# usb.net
KiCad netlist of a schematic drawn in Altium Designer
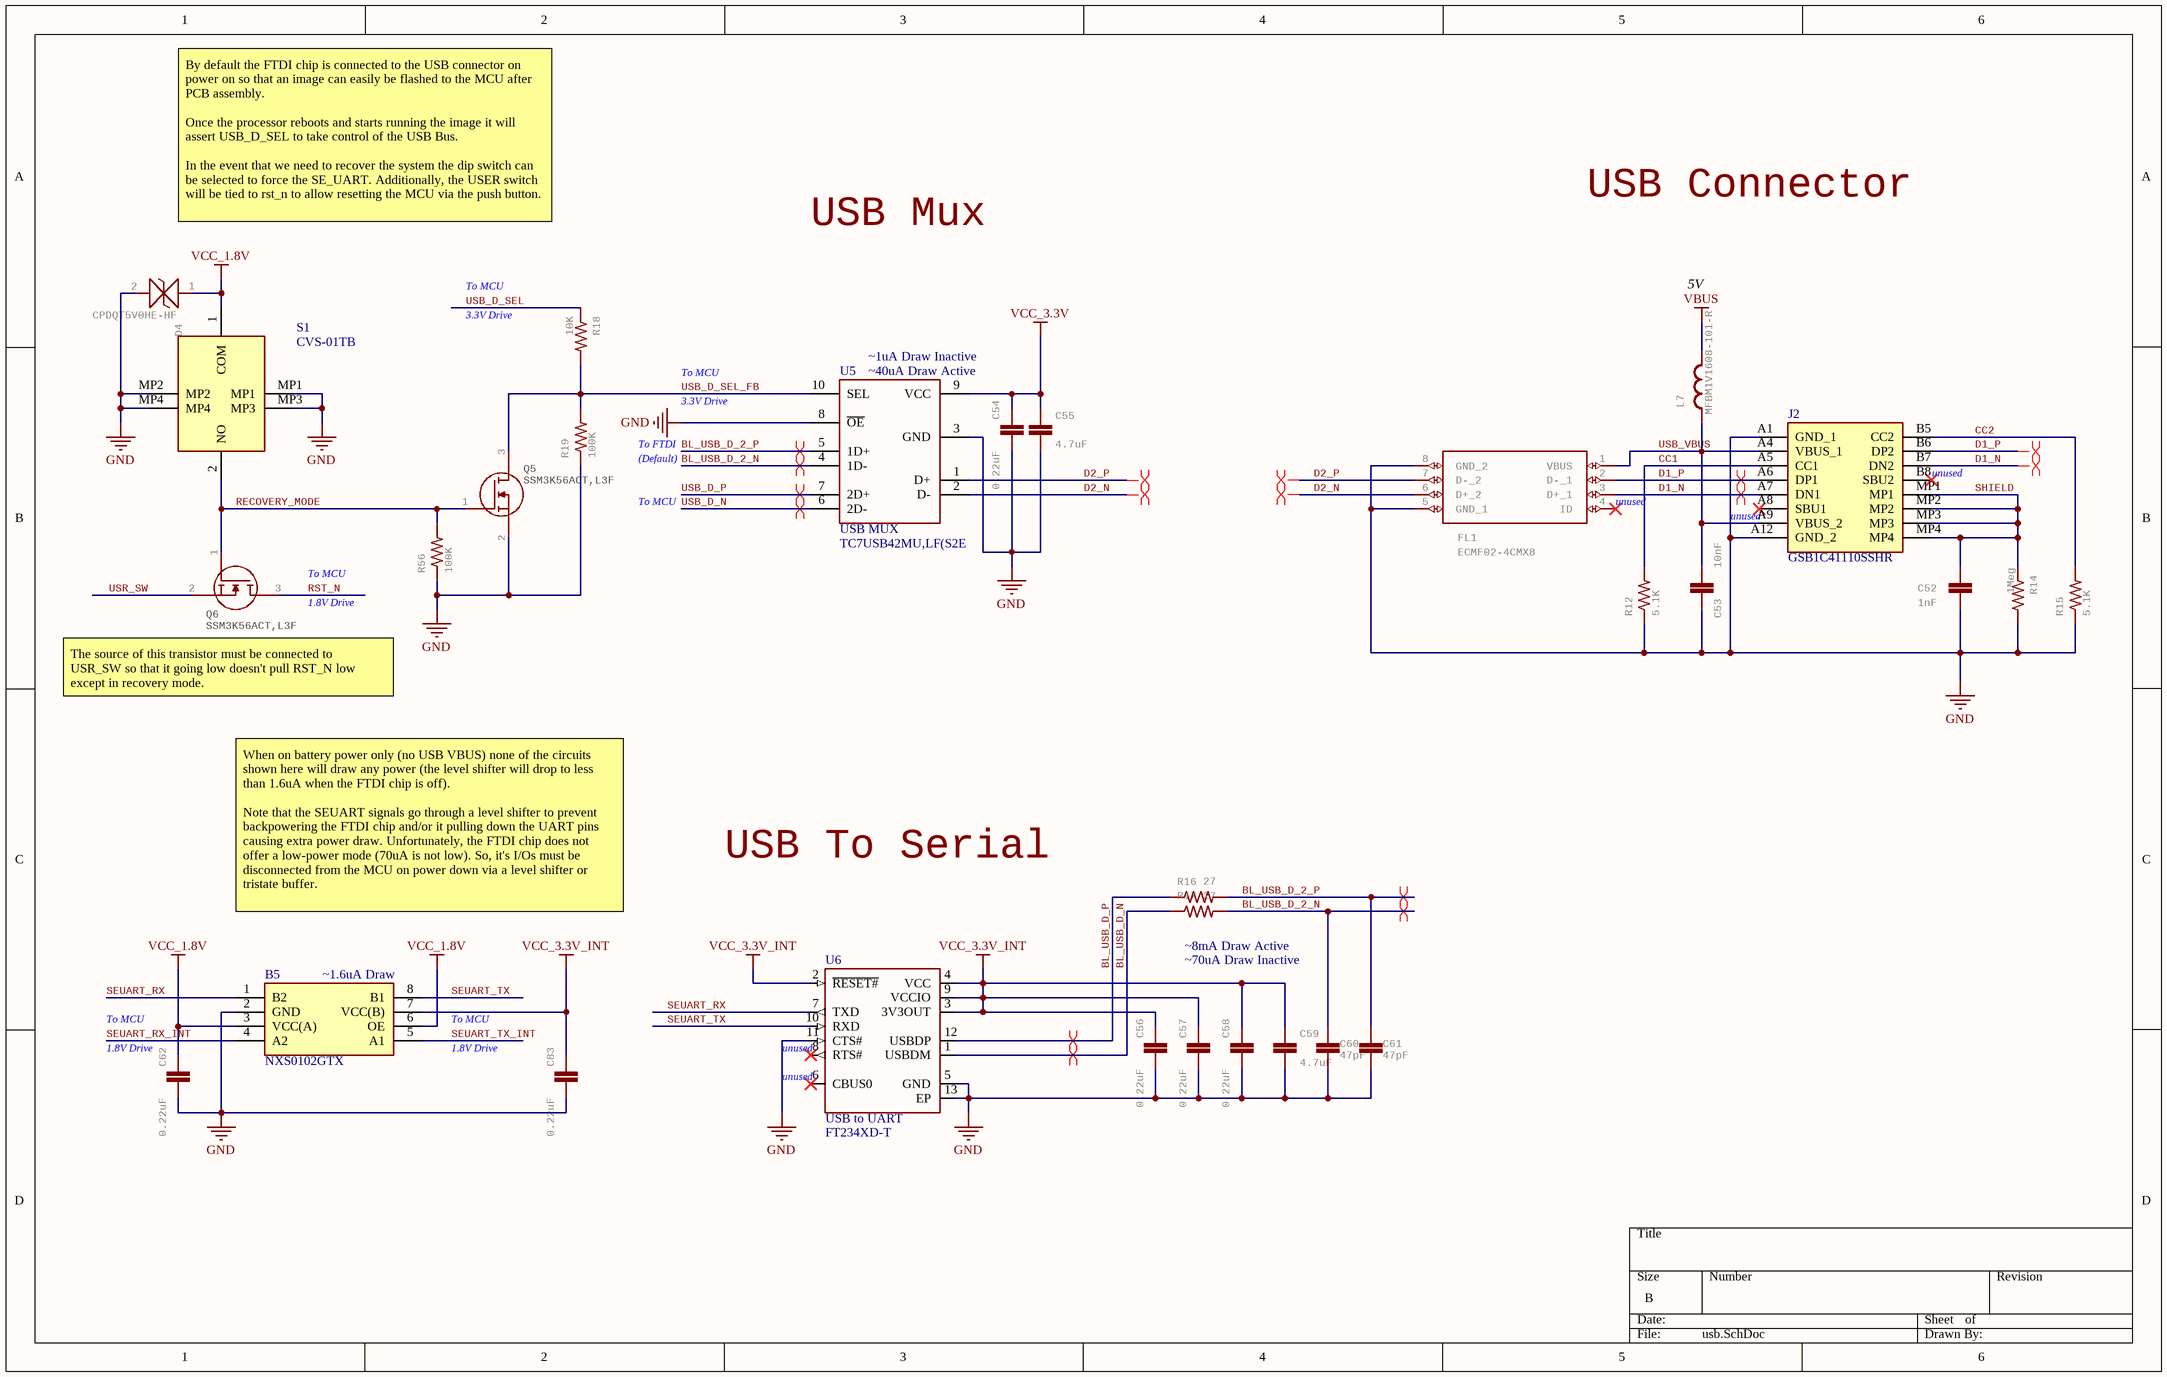
[diagram p0: usb.SchDoc]

(export (version "E")
  (design (tool "Eeschema 10.0.6"))
  (components
    (comp (ref "B5")
      (value "NXS0102GTX")
      (footprint "NXS0102GTX")
      (description "Dual supply translating transceiver; open drain; auto direction sensing")
      (fields (field (name "MOUSER PART NUMBER") "771-NXS0102GTX"))
      (libsource (lib "openmv-ae3") (part "NXS0102GTX"))
    )
    (comp (ref "C52")
      (value "1nF")
      (footprint "0402-CAP")
      (description "Capacitor")
      (fields (field (name "MPN") "VJ0402Y102JXACW1BC") (field (name "LIBRARYNAME") "sfe"))
      (libsource (lib "openmv-ae3") (part "CAP0402-CAP"))
    )
    (comp (ref "C53")
      (value "10nF")
      (footprint "0402-CAP")
      (description "CAPACITOR, European symbol")
      (fields (field (name "MPN") "0402B103K250CT"))
      (libsource (lib "") (part "C-EUC0201_1"))
    )
    (comp (ref "C54")
      (value "0.22uF")
      (footprint "C0201")
      (description "CAPACITOR, European symbol")
      (fields (field (name "MPN") "GRM033R60J224ME15D"))
      (libsource (lib "openmv-ae3") (part "C-EUC0201"))
    )
    (comp (ref "C55")
      (value "4.7uF")
      (footprint "0402-CAP")
      (description "CapacitorStandard 0603 ceramic capacitor, and 0.1\" leaded capacitor.")
      (fields (field (name "MPN") "JMK105BBJ475MV-F") (field (name "LIBRARYNAME") "sfe"))
      (libsource (lib "") (part "CAP0402-CAP_1"))
    )
    (comp (ref "C56")
      (value "0.22uF")
      (footprint "C0201")
      (description "CAPACITOR, European symbol")
      (fields (field (name "MPN") "GRM033R60J224ME15D"))
      (libsource (lib "openmv-ae3") (part "C-EUC0201"))
    )
    (comp (ref "C57")
      (value "0.22uF")
      (footprint "C0201")
      (description "CAPACITOR, European symbol")
      (fields (field (name "MPN") "GRM033R60J224ME15D"))
      (libsource (lib "openmv-ae3") (part "C-EUC0201"))
    )
    (comp (ref "C58")
      (value "0.22uF")
      (footprint "C0201")
      (description "CAPACITOR, European symbol")
      (fields (field (name "MPN") "GRM033R60J224ME15D"))
      (libsource (lib "openmv-ae3") (part "C-EUC0201"))
    )
    (comp (ref "C59")
      (value "4.7uF")
      (footprint "0402-CAP")
      (description "CapacitorStandard 0603 ceramic capacitor, and 0.1\" leaded capacitor.")
      (fields (field (name "MPN") "JMK105BBJ475MV-F") (field (name "LIBRARYNAME") "sfe"))
      (libsource (lib "") (part "CAP0402-CAP_1"))
    )
    (comp (ref "C60")
      (value "47pF")
      (footprint "C0201")
      (description "CAPACITOR, European symbol")
      (fields (field (name "MPN") "GRM0335C1H470GA01J"))
      (libsource (lib "") (part "C-EUC0201_1"))
    )
    (comp (ref "C61")
      (value "47pF")
      (footprint "C0201")
      (description "CAPACITOR, European symbol")
      (fields (field (name "MPN") "GRM0335C1H470GA01J"))
      (libsource (lib "") (part "C-EUC0201_1"))
    )
    (comp (ref "C62")
      (value "0.22uF")
      (footprint "C0201")
      (description "CAPACITOR, European symbol")
      (fields (field (name "MPN") "GRM033R60J224ME15D"))
      (libsource (lib "openmv-ae3") (part "C-EUC0201"))
    )
    (comp (ref "C83")
      (value "0.22uF")
      (footprint "C0201")
      (description "CAPACITOR, European symbol")
      (fields (field (name "MPN") "GRM033R60J224ME15D"))
      (libsource (lib "openmv-ae3") (part "C-EUC0201"))
    )
    (comp (ref "D4")
      (value "CPDQT5V0HE-HF")
      (footprint "CPDQT5V0HEHF")
      (description "ESD Suppressors / TVS Diodes DIODE ESD 5VWM 65W 0402/SOD-923F   Source:  Datasheet")
      (fields (field (name "MOUSER_PART_NUMBER") "MOUSER_PART_NUMBER"))
      (libsource (lib "openmv-ae3") (part "CPDQT5V0HE-HF"))
    )
    (comp (ref "FL1")
      (value "ECMF02-4CMX8")
      (footprint "ECMF024CMX8")
      (fields (field (name "MOUSER_PART_NUMBER") "511-ECMF02-4CMX8"))
      (libsource (lib "openmv-ae3") (part "ECMF02-4CMX8"))
    )
    (comp (ref "J2")
      (value "GSB1C41110SSHR")
      (footprint "SamacSys:GSB1C41110SSHR")
      (description "Connector")
      (libsource (lib "openmv-ae3") (part "GSB1C41110SSHR"))
    )
    (comp (ref "L7")
      (value "MFBM1V1608-101-R")
      (footprint "0603-RES")
      (libsource (lib "openmv-ae3") (part "INDUCTOR"))
    )
    (comp (ref "Q5")
      (value "NMOS")
      (footprint "DFN1006")
      (fields (field (name "MPN") "SSM3K56ACT,L3F") (field (name "PART NUMBER") "SSM3K56ACT,L3F"))
      (libsource (lib "openmv-ae3") (part "NMOS"))
    )
    (comp (ref "Q6")
      (value "NMOS")
      (footprint "DFN1006")
      (fields (field (name "MPN") "SSM3K56ACT,L3F") (field (name "PART NUMBER") "SSM3K56ACT,L3F"))
      (libsource (lib "openmv-ae3") (part "NMOS"))
    )
    (comp (ref "R12")
      (value "5.1K")
      (footprint "R0201")
      (description "ResistorBasic schematic elements and footprints for 0603, 1206, and PTH resistors.")
      (fields (field (name "MPN") "AC0201FR-075K1L") (field (name "LIBRARYNAME") "sfe"))
      (libsource (lib "openmv-ae3") (part "RESISTOR0402-RES"))
    )
    (comp (ref "R14")
      (value "1Meg")
      (footprint "0402-RES")
      (description "Resistor")
      (fields (field (name "MPN") "CRCW04021M00FKEDC") (field (name "LIBRARYNAME") "sfe"))
      (libsource (lib "openmv-ae3") (part "RESISTOR0402-RES"))
    )
    (comp (ref "R15")
      (value "5.1K")
      (footprint "R0201")
      (description "ResistorBasic schematic elements and footprints for 0603, 1206, and PTH resistors.")
      (fields (field (name "MPN") "AC0201FR-075K1L") (field (name "LIBRARYNAME") "sfe"))
      (libsource (lib "openmv-ae3") (part "RESISTOR0402-RES"))
    )
    (comp (ref "R16")
      (value "27")
      (footprint "R0201")
      (fields (field (name "MPN") "RC0201JR-0727RL") (field (name "LIBRARYNAME") "sfe"))
      (libsource (lib "openmv-ae3") (part "RESISTOR0402-RES"))
    )
    (comp (ref "R17")
      (value "27")
      (footprint "R0201")
      (fields (field (name "MPN") "RC0201JR-0727RL") (field (name "LIBRARYNAME") "sfe"))
      (libsource (lib "openmv-ae3") (part "RESISTOR0402-RES"))
    )
    (comp (ref "R18")
      (value "10K")
      (footprint "R0201")
      (fields (field (name "MPN") "RMCF0201FT10K0") (field (name "LIBRARYNAME") "sfe"))
      (libsource (lib "openmv-ae3") (part "RESISTOR0402-RES"))
    )
    (comp (ref "R19")
      (value "100K")
      (footprint "R0201")
      (fields (field (name "MPN") "RMCF0201FT100K") (field (name "LIBRARYNAME") "sfe"))
      (libsource (lib "openmv-ae3") (part "RESISTOR0402-RES"))
    )
    (comp (ref "R56")
      (value "100K")
      (footprint "R0201")
      (fields (field (name "MPN") "RMCF0201FT100K") (field (name "LIBRARYNAME") "sfe"))
      (libsource (lib "openmv-ae3") (part "RESISTOR0402-RES"))
    )
    (comp (ref "S1")
      (value "CVS-01TB")
      (footprint "SamacSys:CVS01TB")
      (description "Switch")
      (fields (field (name "MOUSER PART NUMBER") "229-CVS-01TB"))
      (libsource (lib "openmv-ae3") (part "CVS-01TB"))
    )
    (comp (ref "U5")
      (value "USB MUX")
      (footprint "TC7USB42MU,LF(S2E")
      (fields
        (field (name "MF") "Toshiba")
        (field (name "MPN") "TC7USB42MU,LF(S2E")
        (field (name "PART NUMBER") "TC7USB42MU,LF(S2E")
      )
      (libsource (lib "openmv-ae3") (part "TC7USB42MU,LF(S2E"))
    )
    (comp (ref "U6")
      (value "USB to UART")
      (footprint "SON45P300X300X80-13N")
      (description "USB Bridge, USB to UART USB 2.0 UART Interface 12-DFN _3x3_")
      (fields
        (field (name "MF") "FTDI,")
        (field (name "PART NUMBER") "FT234XD-T")
        (field (name "MPN") "FT234XD-T")
      )
      (libsource (lib "openmv-ae3") (part "FT234XD-T"))
    )
  )
  (nets
    (net (code "1") (name "/BL_USB_D_2_N") (class "Default")
      (node (ref "C60") (pin "2") (pinfunction "2_2") (pintype "passive"))
      (node (ref "R17") (pin "2") (pinfunction "2_2") (pintype "passive"))
      (node (ref "U5") (pin "4") (pinfunction "1D-_4") (pintype "passive"))
    )
    (net (code "2") (name "/BL_USB_D_2_P") (class "Default")
      (node (ref "C61") (pin "2") (pinfunction "2_2") (pintype "passive"))
      (node (ref "R16") (pin "2") (pinfunction "2_2") (pintype "passive"))
      (node (ref "U5") (pin "5") (pinfunction "1D+_5") (pintype "passive"))
    )
    (net (code "3") (name "/BL_USB_D_N") (class "Default")
      (node (ref "R17") (pin "1") (pinfunction "1_1") (pintype "passive"))
      (node (ref "U6") (pin "1") (pinfunction "USBDM_1") (pintype "bidirectional"))
    )
    (net (code "4") (name "/BL_USB_D_P") (class "Default")
      (node (ref "R16") (pin "1") (pinfunction "1_1") (pintype "passive"))
      (node (ref "U6") (pin "12") (pinfunction "USBDP_12") (pintype "bidirectional"))
    )
    (net (code "5") (name "/CC1") (class "Default")
      (node (ref "J2") (pin "A5") (pinfunction "CC1_A5") (pintype "passive"))
      (node (ref "R12") (pin "2") (pinfunction "2_2") (pintype "passive"))
    )
    (net (code "6") (name "/CC2") (class "Default")
      (node (ref "J2") (pin "B5") (pinfunction "CC2_B5") (pintype "passive"))
      (node (ref "R15") (pin "2") (pinfunction "2_2") (pintype "passive"))
    )
    (net (code "7") (name "/D1_N") (class "Default")
      (node (ref "FL1") (pin "3") (pinfunction "D+_1_3") (pintype "bidirectional"))
      (node (ref "J2") (pin "A7") (pinfunction "DN1_A7") (pintype "passive"))
      (node (ref "J2") (pin "B7") (pinfunction "DN2_B7") (pintype "passive"))
    )
    (net (code "8") (name "/D1_P") (class "Default")
      (node (ref "FL1") (pin "2") (pinfunction "D-_1_2") (pintype "bidirectional"))
      (node (ref "J2") (pin "A6") (pinfunction "DP1_A6") (pintype "passive"))
      (node (ref "J2") (pin "B6") (pinfunction "DP2_B6") (pintype "passive"))
    )
    (net (code "9") (name "/D2_N") (class "Default")
      (node (ref "FL1") (pin "6") (pinfunction "D+_2_6") (pintype "bidirectional"))
      (node (ref "U5") (pin "2") (pinfunction "D-_2") (pintype "passive"))
    )
    (net (code "10") (name "/D2_P") (class "Default")
      (node (ref "FL1") (pin "7") (pinfunction "D-_2_7") (pintype "bidirectional"))
      (node (ref "U5") (pin "1") (pinfunction "D+_1") (pintype "passive"))
    )
    (net (code "11") (name "/RECOVERY_MODE") (class "Default")
      (node (ref "Q5") (pin "1") (pinfunction "G_1") (pintype "bidirectional"))
      (node (ref "Q6") (pin "1") (pinfunction "G_1") (pintype "bidirectional"))
      (node (ref "R56") (pin "2") (pinfunction "2_2") (pintype "passive"))
      (node (ref "S1") (pin "2") (pinfunction "NO_2") (pintype "passive"))
    )
    (net (code "12") (name "/RST_N") (class "Default")
      (node (ref "Q6") (pin "3") (pinfunction "D_3") (pintype "bidirectional"))
    )
    (net (code "13") (name "/SEUART_RX") (class "Default")
      (node (ref "B5") (pin "1") (pinfunction "B2_1") (pintype "passive"))
      (node (ref "U6") (pin "7") (pinfunction "TXD_7") (pintype "output"))
    )
    (net (code "14") (name "/SEUART_RX_INT") (class "Default")
      (node (ref "B5") (pin "4") (pinfunction "A2_4") (pintype "passive"))
    )
    (net (code "15") (name "/SEUART_TX") (class "Default")
      (node (ref "B5") (pin "8") (pinfunction "B1_8") (pintype "passive"))
      (node (ref "U6") (pin "10") (pinfunction "RXD_10") (pintype "input"))
    )
    (net (code "16") (name "/SEUART_TX_INT") (class "Default")
      (node (ref "B5") (pin "5") (pinfunction "A1_5") (pintype "passive"))
    )
    (net (code "17") (name "/SHIELD") (class "Default")
      (node (ref "C52") (pin "1") (pinfunction "1_1") (pintype "passive"))
      (node (ref "J2") (pin "MP1") (pinfunction "MP1_MP1") (pintype "passive"))
      (node (ref "J2") (pin "MP2") (pinfunction "MP2_MP2") (pintype "passive"))
      (node (ref "J2") (pin "MP3") (pinfunction "MP3_MP3") (pintype "passive"))
      (node (ref "J2") (pin "MP4") (pinfunction "MP4_MP4") (pintype "passive"))
      (node (ref "R14") (pin "1") (pinfunction "1_1") (pintype "passive"))
    )
    (net (code "18") (name "/USB_D_N") (class "Default")
      (node (ref "U5") (pin "6") (pinfunction "2D-_6") (pintype "passive"))
    )
    (net (code "19") (name "/USB_D_P") (class "Default")
      (node (ref "U5") (pin "7") (pinfunction "2D+_7") (pintype "passive"))
    )
    (net (code "20") (name "/USB_D_SEL") (class "Default")
      (node (ref "R18") (pin "1") (pinfunction "1_1") (pintype "passive"))
    )
    (net (code "21") (name "/USB_D_SEL_FB") (class "Default")
      (node (ref "Q5") (pin "3") (pinfunction "D_3") (pintype "bidirectional"))
      (node (ref "R18") (pin "2") (pinfunction "2_2") (pintype "passive"))
      (node (ref "R19") (pin "2") (pinfunction "2_2") (pintype "passive"))
      (node (ref "U5") (pin "10") (pinfunction "SEL_10") (pintype "passive"))
    )
    (net (code "22") (name "/USB_VBUS") (class "Default")
      (node (ref "C53") (pin "2") (pinfunction "2_2") (pintype "passive"))
      (node (ref "FL1") (pin "1") (pinfunction "VBUS_1") (pintype "bidirectional"))
      (node (ref "J2") (pin "A4") (pinfunction "VBUS_1_A4") (pintype "passive"))
      (node (ref "J2") (pin "A9") (pinfunction "VBUS_2_A9") (pintype "passive"))
      (node (ref "L7") (pin "1") (pinfunction "1_1") (pintype "passive"))
    )
    (net (code "23") (name "/USR_SW") (class "Default")
      (node (ref "Q6") (pin "2") (pinfunction "S_2") (pintype "bidirectional"))
    )
    (net (code "24") (name "GND") (class "Default")
      (node (ref "B5") (pin "2") (pinfunction "GND_2") (pintype "passive"))
      (node (ref "C52") (pin "2") (pinfunction "2_2") (pintype "passive"))
      (node (ref "C53") (pin "1") (pinfunction "1_1") (pintype "passive"))
      (node (ref "C54") (pin "2") (pinfunction "2_2") (pintype "passive"))
      (node (ref "C55") (pin "1") (pinfunction "1_1") (pintype "passive"))
      (node (ref "C56") (pin "2") (pinfunction "2_2") (pintype "passive"))
      (node (ref "C57") (pin "2") (pinfunction "2_2") (pintype "passive"))
      (node (ref "C58") (pin "2") (pinfunction "2_2") (pintype "passive"))
      (node (ref "C59") (pin "1") (pinfunction "1_1") (pintype "passive"))
      (node (ref "C60") (pin "1") (pinfunction "1_1") (pintype "passive"))
      (node (ref "C61") (pin "1") (pinfunction "1_1") (pintype "passive"))
      (node (ref "C62") (pin "2") (pinfunction "2_2") (pintype "passive"))
      (node (ref "C83") (pin "2") (pinfunction "2_2") (pintype "passive"))
      (node (ref "D4") (pin "2") (pinfunction "2_2") (pintype "bidirectional"))
      (node (ref "FL1") (pin "5") (pinfunction "GND_1_5") (pintype "bidirectional"))
      (node (ref "FL1") (pin "8") (pinfunction "GND_2_8") (pintype "bidirectional"))
      (node (ref "J2") (pin "A1") (pinfunction "GND_1_A1") (pintype "passive"))
      (node (ref "J2") (pin "A12") (pinfunction "GND_2_A12") (pintype "passive"))
      (node (ref "Q5") (pin "2") (pinfunction "S_2") (pintype "bidirectional"))
      (node (ref "R12") (pin "1") (pinfunction "1_1") (pintype "passive"))
      (node (ref "R14") (pin "2") (pinfunction "2_2") (pintype "passive"))
      (node (ref "R15") (pin "1") (pinfunction "1_1") (pintype "passive"))
      (node (ref "R19") (pin "1") (pinfunction "1_1") (pintype "passive"))
      (node (ref "R56") (pin "1") (pinfunction "1_1") (pintype "passive"))
      (node (ref "S1") (pin "MP1") (pinfunction "MP1_MP1") (pintype "passive"))
      (node (ref "S1") (pin "MP2") (pinfunction "MP2_MP2") (pintype "passive"))
      (node (ref "S1") (pin "MP3") (pinfunction "MP3_MP3") (pintype "passive"))
      (node (ref "S1") (pin "MP4") (pinfunction "MP4_MP4") (pintype "passive"))
      (node (ref "U5") (pin "3") (pinfunction "GND_3") (pintype "passive"))
      (node (ref "U5") (pin "8") (pinfunction "~{OE}_8") (pintype "passive"))
      (node (ref "U6") (pin "11") (pinfunction "CTS#_11") (pintype "input"))
      (node (ref "U6") (pin "13") (pinfunction "EP_13") (pintype "power_in"))
      (node (ref "U6") (pin "5") (pinfunction "GND_5") (pintype "power_in"))
    )
    (net (code "25") (name "VBUS") (class "Default")
      (node (ref "L7") (pin "2") (pinfunction "2_2") (pintype "passive"))
    )
    (net (code "26") (name "VCC_1.8V") (class "Default")
      (node (ref "B5") (pin "3") (pinfunction "VCC(A)_3") (pintype "passive"))
      (node (ref "B5") (pin "6") (pinfunction "OE_6") (pintype "passive"))
      (node (ref "C62") (pin "1") (pinfunction "1_1") (pintype "passive"))
      (node (ref "D4") (pin "1") (pinfunction "1_1") (pintype "bidirectional"))
      (node (ref "S1") (pin "1") (pinfunction "COM_1") (pintype "passive"))
    )
    (net (code "27") (name "VCC_3.3V") (class "Default")
      (node (ref "C54") (pin "1") (pinfunction "1_1") (pintype "passive"))
      (node (ref "C55") (pin "2") (pinfunction "2_2") (pintype "passive"))
      (node (ref "U5") (pin "9") (pinfunction "VCC_9") (pintype "passive"))
    )
    (net (code "28") (name "VCC_3.3V_INT") (class "Default")
      (node (ref "B5") (pin "7") (pinfunction "VCC(B)_7") (pintype "passive"))
      (node (ref "C56") (pin "1") (pinfunction "1_1") (pintype "passive"))
      (node (ref "C57") (pin "1") (pinfunction "1_1") (pintype "passive"))
      (node (ref "C58") (pin "1") (pinfunction "1_1") (pintype "passive"))
      (node (ref "C59") (pin "2") (pinfunction "2_2") (pintype "passive"))
      (node (ref "C83") (pin "1") (pinfunction "1_1") (pintype "passive"))
      (node (ref "U6") (pin "2") (pinfunction "~{RESET#}_2") (pintype "input"))
      (node (ref "U6") (pin "3") (pinfunction "3V3OUT_3") (pintype "power_in"))
      (node (ref "U6") (pin "4") (pinfunction "VCC_4") (pintype "power_in"))
      (node (ref "U6") (pin "9") (pinfunction "VCCIO_9") (pintype "power_in"))
    )
    (net (code "29") (name "unconnected-(FL1-ID-Pad4)") (class "Default")
      (node (ref "FL1") (pin "4") (pinfunction "ID_4") (pintype "bidirectional+no_connect"))
    )
    (net (code "30") (name "unconnected-(J2-SBU1-PadA8)") (class "Default")
      (node (ref "J2") (pin "A8") (pinfunction "SBU1_A8") (pintype "passive+no_connect"))
    )
    (net (code "31") (name "unconnected-(J2-SBU2-PadB8)") (class "Default")
      (node (ref "J2") (pin "B8") (pinfunction "SBU2_B8") (pintype "passive+no_connect"))
    )
    (net (code "32") (name "unconnected-(U6-CBUS0-Pad6)") (class "Default")
      (node (ref "U6") (pin "6") (pinfunction "CBUS0_6") (pintype "bidirectional+no_connect"))
    )
    (net (code "33") (name "unconnected-(U6-RTS#-Pad8)") (class "Default")
      (node (ref "U6") (pin "8") (pinfunction "RTS#_8") (pintype "output+no_connect"))
    )
  )
)
